# 5__schdoc.net
KiCad netlist of a schematic drawn in Altium Designer
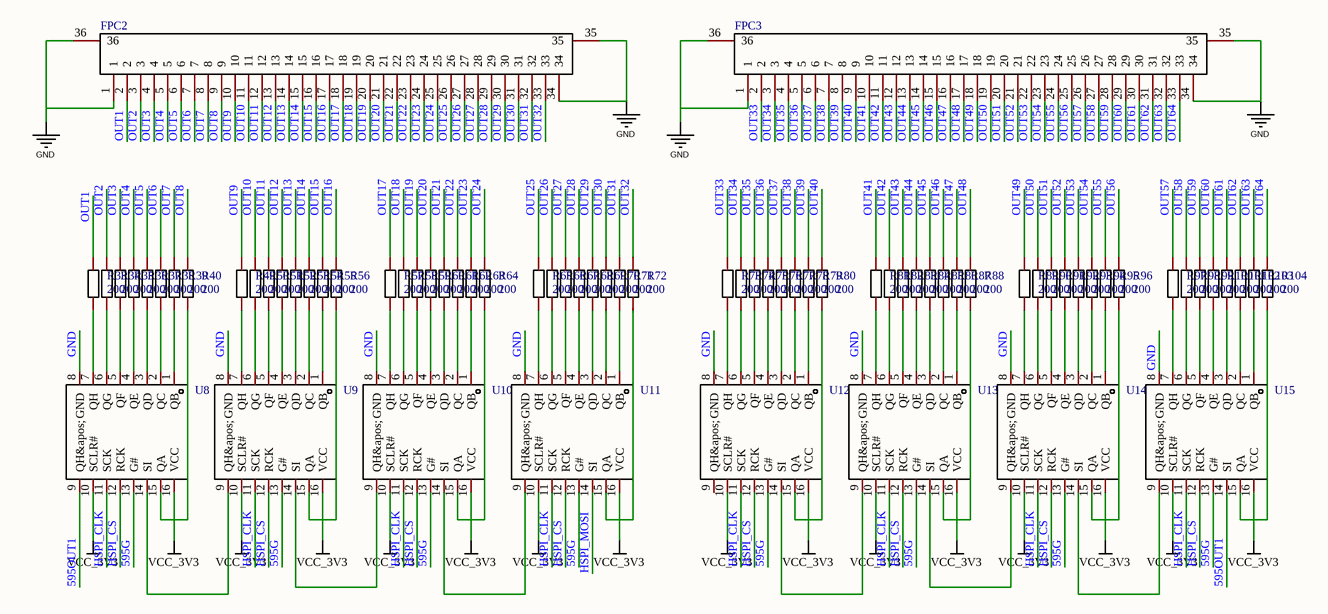
[diagram p0: 5_移位寄存器部分.schdoc.schdoc]

(export (version "E")
  (design (tool "Eeschema 10.0.6"))
  (components
    (comp (ref "FPC2")
      (value "AFC07-S34FCC-00")
      (description "锁定特性:抽屉式;触点类型:下接;触点数量:34P;间距:0.5mm;安装类型:卧贴;")
      (fields (field (name "MANUFACTURER") "JS(钜硕电子)"))
      (libsource (lib "altium-import") (part "root_1_AFC07-S34FCC-00_"))
    )
    (comp (ref "FPC3")
      (value "AFC07-S34FCC-00")
      (description "锁定特性:抽屉式;触点类型:下接;触点数量:34P;间距:0.5mm;安装类型:卧贴;")
      (fields (field (name "MANUFACTURER") "JS(钜硕电子)"))
      (libsource (lib "altium-import") (part "root_1_AFC07-S34FCC-00_"))
    )
    (comp (ref "R33")
      (value "200")
      (fields (field (name "Comment") "Res_0402"))
      (libsource (lib "altium-import") (part "root_1_Res_0402_"))
    )
    (comp (ref "R34")
      (value "200")
      (fields (field (name "Comment") "Res_0402"))
      (libsource (lib "altium-import") (part "root_1_Res_0402_"))
    )
    (comp (ref "R35")
      (value "200")
      (fields (field (name "Comment") "Res_0402"))
      (libsource (lib "altium-import") (part "root_1_Res_0402_"))
    )
    (comp (ref "R36")
      (value "200")
      (fields (field (name "Comment") "Res_0402"))
      (libsource (lib "altium-import") (part "root_1_Res_0402_"))
    )
    (comp (ref "R37")
      (value "200")
      (fields (field (name "Comment") "Res_0402"))
      (libsource (lib "altium-import") (part "root_1_Res_0402_"))
    )
    (comp (ref "R38")
      (value "200")
      (fields (field (name "Comment") "Res_0402"))
      (libsource (lib "altium-import") (part "root_1_Res_0402_"))
    )
    (comp (ref "R39")
      (value "200")
      (fields (field (name "Comment") "Res_0402"))
      (libsource (lib "altium-import") (part "root_1_Res_0402_"))
    )
    (comp (ref "R40")
      (value "200")
      (fields (field (name "Comment") "Res_0402"))
      (libsource (lib "altium-import") (part "root_1_Res_0402_"))
    )
    (comp (ref "R49")
      (value "200")
      (fields (field (name "Comment") "Res_0402"))
      (libsource (lib "altium-import") (part "root_1_Res_0402_"))
    )
    (comp (ref "R50")
      (value "200")
      (fields (field (name "Comment") "Res_0402"))
      (libsource (lib "altium-import") (part "root_1_Res_0402_"))
    )
    (comp (ref "R51")
      (value "200")
      (fields (field (name "Comment") "Res_0402"))
      (libsource (lib "altium-import") (part "root_1_Res_0402_"))
    )
    (comp (ref "R52")
      (value "200")
      (fields (field (name "Comment") "Res_0402"))
      (libsource (lib "altium-import") (part "root_1_Res_0402_"))
    )
    (comp (ref "R53")
      (value "200")
      (fields (field (name "Comment") "Res_0402"))
      (libsource (lib "altium-import") (part "root_1_Res_0402_"))
    )
    (comp (ref "R54")
      (value "200")
      (fields (field (name "Comment") "Res_0402"))
      (libsource (lib "altium-import") (part "root_1_Res_0402_"))
    )
    (comp (ref "R55")
      (value "200")
      (fields (field (name "Comment") "Res_0402"))
      (libsource (lib "altium-import") (part "root_1_Res_0402_"))
    )
    (comp (ref "R56")
      (value "200")
      (fields (field (name "Comment") "Res_0402"))
      (libsource (lib "altium-import") (part "root_1_Res_0402_"))
    )
    (comp (ref "R57")
      (value "200")
      (fields (field (name "Comment") "Res_0402"))
      (libsource (lib "altium-import") (part "root_1_Res_0402_"))
    )
    (comp (ref "R58")
      (value "200")
      (fields (field (name "Comment") "Res_0402"))
      (libsource (lib "altium-import") (part "root_1_Res_0402_"))
    )
    (comp (ref "R59")
      (value "200")
      (fields (field (name "Comment") "Res_0402"))
      (libsource (lib "altium-import") (part "root_1_Res_0402_"))
    )
    (comp (ref "R60")
      (value "200")
      (fields (field (name "Comment") "Res_0402"))
      (libsource (lib "altium-import") (part "root_1_Res_0402_"))
    )
    (comp (ref "R61")
      (value "200")
      (fields (field (name "Comment") "Res_0402"))
      (libsource (lib "altium-import") (part "root_1_Res_0402_"))
    )
    (comp (ref "R62")
      (value "200")
      (fields (field (name "Comment") "Res_0402"))
      (libsource (lib "altium-import") (part "root_1_Res_0402_"))
    )
    (comp (ref "R63")
      (value "200")
      (fields (field (name "Comment") "Res_0402"))
      (libsource (lib "altium-import") (part "root_1_Res_0402_"))
    )
    (comp (ref "R64")
      (value "200")
      (fields (field (name "Comment") "Res_0402"))
      (libsource (lib "altium-import") (part "root_1_Res_0402_"))
    )
    (comp (ref "R65")
      (value "200")
      (fields (field (name "Comment") "Res_0402"))
      (libsource (lib "altium-import") (part "root_1_Res_0402_"))
    )
    (comp (ref "R66")
      (value "200")
      (fields (field (name "Comment") "Res_0402"))
      (libsource (lib "altium-import") (part "root_1_Res_0402_"))
    )
    (comp (ref "R67")
      (value "200")
      (fields (field (name "Comment") "Res_0402"))
      (libsource (lib "altium-import") (part "root_1_Res_0402_"))
    )
    (comp (ref "R68")
      (value "200")
      (fields (field (name "Comment") "Res_0402"))
      (libsource (lib "altium-import") (part "root_1_Res_0402_"))
    )
    (comp (ref "R69")
      (value "200")
      (fields (field (name "Comment") "Res_0402"))
      (libsource (lib "altium-import") (part "root_1_Res_0402_"))
    )
    (comp (ref "R70")
      (value "200")
      (fields (field (name "Comment") "Res_0402"))
      (libsource (lib "altium-import") (part "root_1_Res_0402_"))
    )
    (comp (ref "R71")
      (value "200")
      (fields (field (name "Comment") "Res_0402"))
      (libsource (lib "altium-import") (part "root_1_Res_0402_"))
    )
    (comp (ref "R72")
      (value "200")
      (fields (field (name "Comment") "Res_0402"))
      (libsource (lib "altium-import") (part "root_1_Res_0402_"))
    )
    (comp (ref "R73")
      (value "200")
      (fields (field (name "Comment") "Res_0402"))
      (libsource (lib "altium-import") (part "root_1_Res_0402_"))
    )
    (comp (ref "R74")
      (value "200")
      (fields (field (name "Comment") "Res_0402"))
      (libsource (lib "altium-import") (part "root_1_Res_0402_"))
    )
    (comp (ref "R75")
      (value "200")
      (fields (field (name "Comment") "Res_0402"))
      (libsource (lib "altium-import") (part "root_1_Res_0402_"))
    )
    (comp (ref "R76")
      (value "200")
      (fields (field (name "Comment") "Res_0402"))
      (libsource (lib "altium-import") (part "root_1_Res_0402_"))
    )
    (comp (ref "R77")
      (value "200")
      (fields (field (name "Comment") "Res_0402"))
      (libsource (lib "altium-import") (part "root_1_Res_0402_"))
    )
    (comp (ref "R78")
      (value "200")
      (fields (field (name "Comment") "Res_0402"))
      (libsource (lib "altium-import") (part "root_1_Res_0402_"))
    )
    (comp (ref "R79")
      (value "200")
      (fields (field (name "Comment") "Res_0402"))
      (libsource (lib "altium-import") (part "root_1_Res_0402_"))
    )
    (comp (ref "R80")
      (value "200")
      (fields (field (name "Comment") "Res_0402"))
      (libsource (lib "altium-import") (part "root_1_Res_0402_"))
    )
    (comp (ref "R81")
      (value "200")
      (fields (field (name "Comment") "Res_0402"))
      (libsource (lib "altium-import") (part "root_1_Res_0402_"))
    )
    (comp (ref "R82")
      (value "200")
      (fields (field (name "Comment") "Res_0402"))
      (libsource (lib "altium-import") (part "root_1_Res_0402_"))
    )
    (comp (ref "R83")
      (value "200")
      (fields (field (name "Comment") "Res_0402"))
      (libsource (lib "altium-import") (part "root_1_Res_0402_"))
    )
    (comp (ref "R84")
      (value "200")
      (fields (field (name "Comment") "Res_0402"))
      (libsource (lib "altium-import") (part "root_1_Res_0402_"))
    )
    (comp (ref "R85")
      (value "200")
      (fields (field (name "Comment") "Res_0402"))
      (libsource (lib "altium-import") (part "root_1_Res_0402_"))
    )
    (comp (ref "R86")
      (value "200")
      (fields (field (name "Comment") "Res_0402"))
      (libsource (lib "altium-import") (part "root_1_Res_0402_"))
    )
    (comp (ref "R87")
      (value "200")
      (fields (field (name "Comment") "Res_0402"))
      (libsource (lib "altium-import") (part "root_1_Res_0402_"))
    )
    (comp (ref "R88")
      (value "200")
      (fields (field (name "Comment") "Res_0402"))
      (libsource (lib "altium-import") (part "root_1_Res_0402_"))
    )
    (comp (ref "R89")
      (value "200")
      (fields (field (name "Comment") "Res_0402"))
      (libsource (lib "altium-import") (part "root_1_Res_0402_"))
    )
    (comp (ref "R90")
      (value "200")
      (fields (field (name "Comment") "Res_0402"))
      (libsource (lib "altium-import") (part "root_1_Res_0402_"))
    )
    (comp (ref "R91")
      (value "200")
      (fields (field (name "Comment") "Res_0402"))
      (libsource (lib "altium-import") (part "root_1_Res_0402_"))
    )
    (comp (ref "R92")
      (value "200")
      (fields (field (name "Comment") "Res_0402"))
      (libsource (lib "altium-import") (part "root_1_Res_0402_"))
    )
    (comp (ref "R93")
      (value "200")
      (fields (field (name "Comment") "Res_0402"))
      (libsource (lib "altium-import") (part "root_1_Res_0402_"))
    )
    (comp (ref "R94")
      (value "200")
      (fields (field (name "Comment") "Res_0402"))
      (libsource (lib "altium-import") (part "root_1_Res_0402_"))
    )
    (comp (ref "R95")
      (value "200")
      (fields (field (name "Comment") "Res_0402"))
      (libsource (lib "altium-import") (part "root_1_Res_0402_"))
    )
    (comp (ref "R96")
      (value "200")
      (fields (field (name "Comment") "Res_0402"))
      (libsource (lib "altium-import") (part "root_1_Res_0402_"))
    )
    (comp (ref "R97")
      (value "200")
      (fields (field (name "Comment") "Res_0402"))
      (libsource (lib "altium-import") (part "root_1_Res_0402_"))
    )
    (comp (ref "R98")
      (value "200")
      (fields (field (name "Comment") "Res_0402"))
      (libsource (lib "altium-import") (part "root_1_Res_0402_"))
    )
    (comp (ref "R99")
      (value "200")
      (fields (field (name "Comment") "Res_0402"))
      (libsource (lib "altium-import") (part "root_1_Res_0402_"))
    )
    (comp (ref "R100")
      (value "200")
      (fields (field (name "Comment") "Res_0402"))
      (libsource (lib "altium-import") (part "root_1_Res_0402_"))
    )
    (comp (ref "R101")
      (value "200")
      (fields (field (name "Comment") "Res_0402"))
      (libsource (lib "altium-import") (part "root_1_Res_0402_"))
    )
    (comp (ref "R102")
      (value "200")
      (fields (field (name "Comment") "Res_0402"))
      (libsource (lib "altium-import") (part "root_1_Res_0402_"))
    )
    (comp (ref "R103")
      (value "200")
      (fields (field (name "Comment") "Res_0402"))
      (libsource (lib "altium-import") (part "root_1_Res_0402_"))
    )
    (comp (ref "R104")
      (value "200")
      (fields (field (name "Comment") "Res_0402"))
      (libsource (lib "altium-import") (part "root_1_Res_0402_"))
    )
    (comp (ref "U8")
      (value "74HC595D_C431479")
      (description "功能:串行至串行或并行;电源电压:2V~6V;元件数:1;每个元件位数:8;")
      (fields (field (name "MANUFACTURER") "TOSHIBA(东芝)") (field (name "MANUFACTURER PART") "74HC595D"))
      (libsource (lib "altium-import") (part "root_3_74HC595D_C431479_"))
    )
    (comp (ref "U9")
      (value "74HC595D_C431479")
      (description "功能:串行至串行或并行;电源电压:2V~6V;元件数:1;每个元件位数:8;")
      (fields (field (name "MANUFACTURER") "TOSHIBA(东芝)") (field (name "MANUFACTURER PART") "74HC595D"))
      (libsource (lib "altium-import") (part "root_3_74HC595D_C431479_"))
    )
    (comp (ref "U10")
      (value "74HC595D_C431479")
      (description "功能:串行至串行或并行;电源电压:2V~6V;元件数:1;每个元件位数:8;")
      (fields (field (name "MANUFACTURER") "TOSHIBA(东芝)") (field (name "MANUFACTURER PART") "74HC595D"))
      (libsource (lib "altium-import") (part "root_3_74HC595D_C431479_"))
    )
    (comp (ref "U11")
      (value "74HC595D_C431479")
      (description "功能:串行至串行或并行;电源电压:2V~6V;元件数:1;每个元件位数:8;")
      (fields (field (name "MANUFACTURER") "TOSHIBA(东芝)") (field (name "MANUFACTURER PART") "74HC595D"))
      (libsource (lib "altium-import") (part "root_3_74HC595D_C431479_"))
    )
    (comp (ref "U12")
      (value "74HC595D_C431479")
      (description "功能:串行至串行或并行;电源电压:2V~6V;元件数:1;每个元件位数:8;")
      (fields (field (name "MANUFACTURER") "TOSHIBA(东芝)") (field (name "MANUFACTURER PART") "74HC595D"))
      (libsource (lib "altium-import") (part "root_3_74HC595D_C431479_"))
    )
    (comp (ref "U13")
      (value "74HC595D_C431479")
      (description "功能:串行至串行或并行;电源电压:2V~6V;元件数:1;每个元件位数:8;")
      (fields (field (name "MANUFACTURER") "TOSHIBA(东芝)") (field (name "MANUFACTURER PART") "74HC595D"))
      (libsource (lib "altium-import") (part "root_3_74HC595D_C431479_"))
    )
    (comp (ref "U14")
      (value "74HC595D_C431479")
      (description "功能:串行至串行或并行;电源电压:2V~6V;元件数:1;每个元件位数:8;")
      (fields (field (name "MANUFACTURER") "TOSHIBA(东芝)") (field (name "MANUFACTURER PART") "74HC595D"))
      (libsource (lib "altium-import") (part "root_3_74HC595D_C431479_"))
    )
    (comp (ref "U15")
      (value "74HC595D_C431479")
      (description "功能:串行至串行或并行;电源电压:2V~6V;元件数:1;每个元件位数:8;")
      (fields (field (name "MANUFACTURER") "TOSHIBA(东芝)") (field (name "MANUFACTURER PART") "74HC595D"))
      (libsource (lib "altium-import") (part "root_3_74HC595D_C431479_"))
    )
  )
  (nets
    (net (code "1") (name "/595G") (class "Default")
      (node (ref "U10") (pin "13") (pinfunction "G#_13") (pintype "passive"))
      (node (ref "U11") (pin "13") (pinfunction "G#_13") (pintype "passive"))
      (node (ref "U12") (pin "13") (pinfunction "G#_13") (pintype "passive"))
      (node (ref "U13") (pin "13") (pinfunction "G#_13") (pintype "passive"))
      (node (ref "U14") (pin "13") (pinfunction "G#_13") (pintype "passive"))
      (node (ref "U15") (pin "13") (pinfunction "G#_13") (pintype "passive"))
      (node (ref "U8") (pin "13") (pinfunction "G#_13") (pintype "passive"))
      (node (ref "U9") (pin "13") (pinfunction "G#_13") (pintype "passive"))
    )
    (net (code "2") (name "/595OUT1") (class "Default")
      (node (ref "U15") (pin "14") (pinfunction "SI_14") (pintype "passive"))
      (node (ref "U8") (pin "9") (pinfunction "QH&apos;_9") (pintype "passive"))
    )
    (net (code "3") (name "/HSPI_CLK") (class "Default")
      (node (ref "U10") (pin "11") (pinfunction "SCK_11") (pintype "passive"))
      (node (ref "U11") (pin "11") (pinfunction "SCK_11") (pintype "passive"))
      (node (ref "U12") (pin "11") (pinfunction "SCK_11") (pintype "passive"))
      (node (ref "U13") (pin "11") (pinfunction "SCK_11") (pintype "passive"))
      (node (ref "U14") (pin "11") (pinfunction "SCK_11") (pintype "passive"))
      (node (ref "U15") (pin "11") (pinfunction "SCK_11") (pintype "passive"))
      (node (ref "U8") (pin "11") (pinfunction "SCK_11") (pintype "passive"))
      (node (ref "U9") (pin "11") (pinfunction "SCK_11") (pintype "passive"))
    )
    (net (code "4") (name "/HSPI_CS") (class "Default")
      (node (ref "U10") (pin "12") (pinfunction "RCK_12") (pintype "passive"))
      (node (ref "U11") (pin "12") (pinfunction "RCK_12") (pintype "passive"))
      (node (ref "U12") (pin "12") (pinfunction "RCK_12") (pintype "passive"))
      (node (ref "U13") (pin "12") (pinfunction "RCK_12") (pintype "passive"))
      (node (ref "U14") (pin "12") (pinfunction "RCK_12") (pintype "passive"))
      (node (ref "U15") (pin "12") (pinfunction "RCK_12") (pintype "passive"))
      (node (ref "U8") (pin "12") (pinfunction "RCK_12") (pintype "passive"))
      (node (ref "U9") (pin "12") (pinfunction "RCK_12") (pintype "passive"))
    )
    (net (code "5") (name "/HSPI_MOSI") (class "Default")
      (node (ref "U11") (pin "14") (pinfunction "SI_14") (pintype "passive"))
    )
    (net (code "6") (name "/OUT1") (class "Default")
      (node (ref "FPC2") (pin "2") (pinfunction "2_2") (pintype "passive"))
      (node (ref "R33") (pin "2") (pinfunction "2_2") (pintype "passive"))
    )
    (net (code "7") (name "/OUT2") (class "Default")
      (node (ref "FPC2") (pin "3") (pinfunction "3_3") (pintype "passive"))
      (node (ref "R34") (pin "2") (pinfunction "2_2") (pintype "passive"))
    )
    (net (code "8") (name "/OUT3") (class "Default")
      (node (ref "FPC2") (pin "4") (pinfunction "4_4") (pintype "passive"))
      (node (ref "R35") (pin "2") (pinfunction "2_2") (pintype "passive"))
    )
    (net (code "9") (name "/OUT4") (class "Default")
      (node (ref "FPC2") (pin "5") (pinfunction "5_5") (pintype "passive"))
      (node (ref "R36") (pin "2") (pinfunction "2_2") (pintype "passive"))
    )
    (net (code "10") (name "/OUT5") (class "Default")
      (node (ref "FPC2") (pin "6") (pinfunction "6_6") (pintype "passive"))
      (node (ref "R37") (pin "2") (pinfunction "2_2") (pintype "passive"))
    )
    (net (code "11") (name "/OUT6") (class "Default")
      (node (ref "FPC2") (pin "7") (pinfunction "7_7") (pintype "passive"))
      (node (ref "R38") (pin "2") (pinfunction "2_2") (pintype "passive"))
    )
    (net (code "12") (name "/OUT7") (class "Default")
      (node (ref "FPC2") (pin "8") (pinfunction "8_8") (pintype "passive"))
      (node (ref "R39") (pin "2") (pinfunction "2_2") (pintype "passive"))
    )
    (net (code "13") (name "/OUT8") (class "Default")
      (node (ref "FPC2") (pin "9") (pinfunction "9_9") (pintype "passive"))
      (node (ref "R40") (pin "2") (pinfunction "2_2") (pintype "passive"))
    )
    (net (code "14") (name "/OUT9") (class "Default")
      (node (ref "FPC2") (pin "10") (pinfunction "10_10") (pintype "passive"))
      (node (ref "R49") (pin "2") (pinfunction "2_2") (pintype "passive"))
    )
    (net (code "15") (name "/OUT10") (class "Default")
      (node (ref "FPC2") (pin "11") (pinfunction "11_11") (pintype "passive"))
      (node (ref "R50") (pin "2") (pinfunction "2_2") (pintype "passive"))
    )
    (net (code "16") (name "/OUT11") (class "Default")
      (node (ref "FPC2") (pin "12") (pinfunction "12_12") (pintype "passive"))
      (node (ref "R51") (pin "2") (pinfunction "2_2") (pintype "passive"))
    )
    (net (code "17") (name "/OUT12") (class "Default")
      (node (ref "FPC2") (pin "13") (pinfunction "13_13") (pintype "passive"))
      (node (ref "R52") (pin "2") (pinfunction "2_2") (pintype "passive"))
    )
    (net (code "18") (name "/OUT13") (class "Default")
      (node (ref "FPC2") (pin "14") (pinfunction "14_14") (pintype "passive"))
      (node (ref "R53") (pin "2") (pinfunction "2_2") (pintype "passive"))
    )
    (net (code "19") (name "/OUT14") (class "Default")
      (node (ref "FPC2") (pin "15") (pinfunction "15_15") (pintype "passive"))
      (node (ref "R54") (pin "2") (pinfunction "2_2") (pintype "passive"))
    )
    (net (code "20") (name "/OUT15") (class "Default")
      (node (ref "FPC2") (pin "16") (pinfunction "16_16") (pintype "passive"))
      (node (ref "R55") (pin "2") (pinfunction "2_2") (pintype "passive"))
    )
    (net (code "21") (name "/OUT16") (class "Default")
      (node (ref "FPC2") (pin "17") (pinfunction "17_17") (pintype "passive"))
      (node (ref "R56") (pin "2") (pinfunction "2_2") (pintype "passive"))
    )
    (net (code "22") (name "/OUT17") (class "Default")
      (node (ref "FPC2") (pin "18") (pinfunction "18_18") (pintype "passive"))
      (node (ref "R57") (pin "2") (pinfunction "2_2") (pintype "passive"))
    )
    (net (code "23") (name "/OUT18") (class "Default")
      (node (ref "FPC2") (pin "19") (pinfunction "19_19") (pintype "passive"))
      (node (ref "R58") (pin "2") (pinfunction "2_2") (pintype "passive"))
    )
    (net (code "24") (name "/OUT19") (class "Default")
      (node (ref "FPC2") (pin "20") (pinfunction "20_20") (pintype "passive"))
      (node (ref "R59") (pin "2") (pinfunction "2_2") (pintype "passive"))
    )
    (net (code "25") (name "/OUT20") (class "Default")
      (node (ref "FPC2") (pin "21") (pinfunction "21_21") (pintype "passive"))
      (node (ref "R60") (pin "2") (pinfunction "2_2") (pintype "passive"))
    )
    (net (code "26") (name "/OUT21") (class "Default")
      (node (ref "FPC2") (pin "22") (pinfunction "22_22") (pintype "passive"))
      (node (ref "R61") (pin "2") (pinfunction "2_2") (pintype "passive"))
    )
    (net (code "27") (name "/OUT22") (class "Default")
      (node (ref "FPC2") (pin "23") (pinfunction "23_23") (pintype "passive"))
      (node (ref "R62") (pin "2") (pinfunction "2_2") (pintype "passive"))
    )
    (net (code "28") (name "/OUT23") (class "Default")
      (node (ref "FPC2") (pin "24") (pinfunction "24_24") (pintype "passive"))
      (node (ref "R63") (pin "2") (pinfunction "2_2") (pintype "passive"))
    )
    (net (code "29") (name "/OUT24") (class "Default")
      (node (ref "FPC2") (pin "25") (pinfunction "25_25") (pintype "passive"))
      (node (ref "R64") (pin "2") (pinfunction "2_2") (pintype "passive"))
    )
    (net (code "30") (name "/OUT25") (class "Default")
      (node (ref "FPC2") (pin "26") (pinfunction "26_26") (pintype "passive"))
      (node (ref "R65") (pin "2") (pinfunction "2_2") (pintype "passive"))
    )
    (net (code "31") (name "/OUT26") (class "Default")
      (node (ref "FPC2") (pin "27") (pinfunction "27_27") (pintype "passive"))
      (node (ref "R66") (pin "2") (pinfunction "2_2") (pintype "passive"))
    )
    (net (code "32") (name "/OUT27") (class "Default")
      (node (ref "FPC2") (pin "28") (pinfunction "28_28") (pintype "passive"))
      (node (ref "R67") (pin "2") (pinfunction "2_2") (pintype "passive"))
    )
    (net (code "33") (name "/OUT28") (class "Default")
      (node (ref "FPC2") (pin "29") (pinfunction "29_29") (pintype "passive"))
      (node (ref "R68") (pin "2") (pinfunction "2_2") (pintype "passive"))
    )
    (net (code "34") (name "/OUT29") (class "Default")
      (node (ref "FPC2") (pin "30") (pinfunction "30_30") (pintype "passive"))
      (node (ref "R69") (pin "2") (pinfunction "2_2") (pintype "passive"))
    )
    (net (code "35") (name "/OUT30") (class "Default")
      (node (ref "FPC2") (pin "31") (pinfunction "31_31") (pintype "passive"))
      (node (ref "R70") (pin "2") (pinfunction "2_2") (pintype "passive"))
    )
    (net (code "36") (name "/OUT31") (class "Default")
      (node (ref "FPC2") (pin "32") (pinfunction "32_32") (pintype "passive"))
      (node (ref "R71") (pin "2") (pinfunction "2_2") (pintype "passive"))
    )
    (net (code "37") (name "/OUT32") (class "Default")
      (node (ref "FPC2") (pin "33") (pinfunction "33_33") (pintype "passive"))
      (node (ref "R72") (pin "2") (pinfunction "2_2") (pintype "passive"))
    )
    (net (code "38") (name "/OUT33") (class "Default")
      (node (ref "FPC3") (pin "2") (pinfunction "2_2") (pintype "passive"))
      (node (ref "R73") (pin "2") (pinfunction "2_2") (pintype "passive"))
    )
    (net (code "39") (name "/OUT34") (class "Default")
      (node (ref "FPC3") (pin "3") (pinfunction "3_3") (pintype "passive"))
      (node (ref "R74") (pin "2") (pinfunction "2_2") (pintype "passive"))
    )
    (net (code "40") (name "/OUT35") (class "Default")
      (node (ref "FPC3") (pin "4") (pinfunction "4_4") (pintype "passive"))
      (node (ref "R75") (pin "2") (pinfunction "2_2") (pintype "passive"))
    )
    (net (code "41") (name "/OUT36") (class "Default")
      (node (ref "FPC3") (pin "5") (pinfunction "5_5") (pintype "passive"))
      (node (ref "R76") (pin "2") (pinfunction "2_2") (pintype "passive"))
    )
    (net (code "42") (name "/OUT37") (class "Default")
      (node (ref "FPC3") (pin "6") (pinfunction "6_6") (pintype "passive"))
      (node (ref "R77") (pin "2") (pinfunction "2_2") (pintype "passive"))
    )
    (net (code "43") (name "/OUT38") (class "Default")
      (node (ref "FPC3") (pin "7") (pinfunction "7_7") (pintype "passive"))
      (node (ref "R78") (pin "2") (pinfunction "2_2") (pintype "passive"))
    )
    (net (code "44") (name "/OUT39") (class "Default")
      (node (ref "FPC3") (pin "8") (pinfunction "8_8") (pintype "passive"))
      (node (ref "R79") (pin "2") (pinfunction "2_2") (pintype "passive"))
    )
    (net (code "45") (name "/OUT40") (class "Default")
      (node (ref "FPC3") (pin "9") (pinfunction "9_9") (pintype "passive"))
      (node (ref "R80") (pin "2") (pinfunction "2_2") (pintype "passive"))
    )
    (net (code "46") (name "/OUT41") (class "Default")
      (node (ref "FPC3") (pin "10") (pinfunction "10_10") (pintype "passive"))
      (node (ref "R81") (pin "2") (pinfunction "2_2") (pintype "passive"))
    )
    (net (code "47") (name "/OUT42") (class "Default")
      (node (ref "FPC3") (pin "11") (pinfunction "11_11") (pintype "passive"))
      (node (ref "R82") (pin "2") (pinfunction "2_2") (pintype "passive"))
    )
    (net (code "48") (name "/OUT43") (class "Default")
      (node (ref "FPC3") (pin "12") (pinfunction "12_12") (pintype "passive"))
      (node (ref "R83") (pin "2") (pinfunction "2_2") (pintype "passive"))
    )
    (net (code "49") (name "/OUT44") (class "Default")
      (node (ref "FPC3") (pin "13") (pinfunction "13_13") (pintype "passive"))
      (node (ref "R84") (pin "2") (pinfunction "2_2") (pintype "passive"))
    )
    (net (code "50") (name "/OUT45") (class "Default")
      (node (ref "FPC3") (pin "14") (pinfunction "14_14") (pintype "passive"))
      (node (ref "R85") (pin "2") (pinfunction "2_2") (pintype "passive"))
    )
    (net (code "51") (name "/OUT46") (class "Default")
      (node (ref "FPC3") (pin "15") (pinfunction "15_15") (pintype "passive"))
      (node (ref "R86") (pin "2") (pinfunction "2_2") (pintype "passive"))
    )
    (net (code "52") (name "/OUT47") (class "Default")
      (node (ref "FPC3") (pin "16") (pinfunction "16_16") (pintype "passive"))
      (node (ref "R87") (pin "2") (pinfunction "2_2") (pintype "passive"))
    )
    (net (code "53") (name "/OUT48") (class "Default")
      (node (ref "FPC3") (pin "17") (pinfunction "17_17") (pintype "passive"))
      (node (ref "R88") (pin "2") (pinfunction "2_2") (pintype "passive"))
    )
    (net (code "54") (name "/OUT49") (class "Default")
      (node (ref "FPC3") (pin "18") (pinfunction "18_18") (pintype "passive"))
      (node (ref "R89") (pin "2") (pinfunction "2_2") (pintype "passive"))
    )
    (net (code "55") (name "/OUT50") (class "Default")
      (node (ref "FPC3") (pin "19") (pinfunction "19_19") (pintype "passive"))
      (node (ref "R90") (pin "2") (pinfunction "2_2") (pintype "passive"))
    )
    (net (code "56") (name "/OUT51") (class "Default")
      (node (ref "FPC3") (pin "20") (pinfunction "20_20") (pintype "passive"))
      (node (ref "R91") (pin "2") (pinfunction "2_2") (pintype "passive"))
    )
    (net (code "57") (name "/OUT52") (class "Default")
      (node (ref "FPC3") (pin "21") (pinfunction "21_21") (pintype "passive"))
      (node (ref "R92") (pin "2") (pinfunction "2_2") (pintype "passive"))
    )
    (net (code "58") (name "/OUT53") (class "Default")
      (node (ref "FPC3") (pin "22") (pinfunction "22_22") (pintype "passive"))
      (node (ref "R93") (pin "2") (pinfunction "2_2") (pintype "passive"))
    )
    (net (code "59") (name "/OUT54") (class "Default")
      (node (ref "FPC3") (pin "23") (pinfunction "23_23") (pintype "passive"))
      (node (ref "R94") (pin "2") (pinfunction "2_2") (pintype "passive"))
    )
    (net (code "60") (name "/OUT55") (class "Default")
      (node (ref "FPC3") (pin "24") (pinfunction "24_24") (pintype "passive"))
      (node (ref "R95") (pin "2") (pinfunction "2_2") (pintype "passive"))
    )
    (net (code "61") (name "/OUT56") (class "Default")
      (node (ref "FPC3") (pin "25") (pinfunction "25_25") (pintype "passive"))
      (node (ref "R96") (pin "2") (pinfunction "2_2") (pintype "passive"))
    )
    (net (code "62") (name "/OUT57") (class "Default")
      (node (ref "FPC3") (pin "26") (pinfunction "26_26") (pintype "passive"))
      (node (ref "R97") (pin "2") (pinfunction "2_2") (pintype "passive"))
    )
    (net (code "63") (name "/OUT58") (class "Default")
      (node (ref "FPC3") (pin "27") (pinfunction "27_27") (pintype "passive"))
      (node (ref "R98") (pin "2") (pinfunction "2_2") (pintype "passive"))
    )
    (net (code "64") (name "/OUT59") (class "Default")
      (node (ref "FPC3") (pin "28") (pinfunction "28_28") (pintype "passive"))
      (node (ref "R99") (pin "2") (pinfunction "2_2") (pintype "passive"))
    )
    (net (code "65") (name "/OUT60") (class "Default")
      (node (ref "FPC3") (pin "29") (pinfunction "29_29") (pintype "passive"))
      (node (ref "R100") (pin "2") (pinfunction "2_2") (pintype "passive"))
    )
    (net (code "66") (name "/OUT61") (class "Default")
      (node (ref "FPC3") (pin "30") (pinfunction "30_30") (pintype "passive"))
      (node (ref "R101") (pin "2") (pinfunction "2_2") (pintype "passive"))
    )
    (net (code "67") (name "/OUT62") (class "Default")
      (node (ref "FPC3") (pin "31") (pinfunction "31_31") (pintype "passive"))
      (node (ref "R102") (pin "2") (pinfunction "2_2") (pintype "passive"))
    )
    (net (code "68") (name "/OUT63") (class "Default")
      (node (ref "FPC3") (pin "32") (pinfunction "32_32") (pintype "passive"))
      (node (ref "R103") (pin "2") (pinfunction "2_2") (pintype "passive"))
    )
    (net (code "69") (name "/OUT64") (class "Default")
      (node (ref "FPC3") (pin "33") (pinfunction "33_33") (pintype "passive"))
      (node (ref "R104") (pin "2") (pinfunction "2_2") (pintype "passive"))
    )
    (net (code "70") (name "GND") (class "Default")
      (node (ref "FPC2") (pin "1") (pinfunction "1_1") (pintype "passive"))
      (node (ref "FPC2") (pin "34") (pinfunction "34_34") (pintype "passive"))
      (node (ref "FPC2") (pin "35") (pinfunction "35_35") (pintype "passive"))
      (node (ref "FPC2") (pin "36") (pinfunction "36_36") (pintype "passive"))
      (node (ref "FPC3") (pin "1") (pinfunction "1_1") (pintype "passive"))
      (node (ref "FPC3") (pin "34") (pinfunction "34_34") (pintype "passive"))
      (node (ref "FPC3") (pin "35") (pinfunction "35_35") (pintype "passive"))
      (node (ref "FPC3") (pin "36") (pinfunction "36_36") (pintype "passive"))
      (node (ref "U10") (pin "8") (pinfunction "GND_8") (pintype "passive"))
      (node (ref "U11") (pin "8") (pinfunction "GND_8") (pintype "passive"))
      (node (ref "U12") (pin "8") (pinfunction "GND_8") (pintype "passive"))
      (node (ref "U13") (pin "8") (pinfunction "GND_8") (pintype "passive"))
      (node (ref "U14") (pin "8") (pinfunction "GND_8") (pintype "passive"))
      (node (ref "U15") (pin "8") (pinfunction "GND_8") (pintype "passive"))
      (node (ref "U8") (pin "8") (pinfunction "GND_8") (pintype "passive"))
      (node (ref "U9") (pin "8") (pinfunction "GND_8") (pintype "passive"))
    )
    (net (code "71") (name "Net-(U8-QA)") (class "Default")
      (node (ref "R40") (pin "1") (pinfunction "1_1") (pintype "passive"))
      (node (ref "U8") (pin "15") (pinfunction "QA_15") (pintype "passive"))
    )
    (net (code "72") (name "Net-(U8-QB)") (class "Default")
      (node (ref "R39") (pin "1") (pinfunction "1_1") (pintype "passive"))
      (node (ref "U8") (pin "1") (pinfunction "QB_1") (pintype "passive"))
    )
    (net (code "73") (name "Net-(U8-QC)") (class "Default")
      (node (ref "R38") (pin "1") (pinfunction "1_1") (pintype "passive"))
      (node (ref "U8") (pin "2") (pinfunction "QC_2") (pintype "passive"))
    )
    (net (code "74") (name "Net-(U8-QD)") (class "Default")
      (node (ref "R37") (pin "1") (pinfunction "1_1") (pintype "passive"))
      (node (ref "U8") (pin "3") (pinfunction "QD_3") (pintype "passive"))
    )
    (net (code "75") (name "Net-(U8-QE)") (class "Default")
      (node (ref "R36") (pin "1") (pinfunction "1_1") (pintype "passive"))
      (node (ref "U8") (pin "4") (pinfunction "QE_4") (pintype "passive"))
    )
    (net (code "76") (name "Net-(U8-QF)") (class "Default")
      (node (ref "R35") (pin "1") (pinfunction "1_1") (pintype "passive"))
      (node (ref "U8") (pin "5") (pinfunction "QF_5") (pintype "passive"))
    )
    (net (code "77") (name "Net-(U8-QG)") (class "Default")
      (node (ref "R34") (pin "1") (pinfunction "1_1") (pintype "passive"))
      (node (ref "U8") (pin "6") (pinfunction "QG_6") (pintype "passive"))
    )
    (net (code "78") (name "Net-(U8-QH)") (class "Default")
      (node (ref "R33") (pin "1") (pinfunction "1_1") (pintype "passive"))
      (node (ref "U8") (pin "7") (pinfunction "QH_7") (pintype "passive"))
    )
    (net (code "79") (name "Net-(U8-SI)") (class "Default")
      (node (ref "U8") (pin "14") (pinfunction "SI_14") (pintype "passive"))
      (node (ref "U9") (pin "9") (pinfunction "QH&apos;_9") (pintype "passive"))
    )
    (net (code "80") (name "Net-(U9-QA)") (class "Default")
      (node (ref "R56") (pin "1") (pinfunction "1_1") (pintype "passive"))
      (node (ref "U9") (pin "15") (pinfunction "QA_15") (pintype "passive"))
    )
    (net (code "81") (name "Net-(U9-QB)") (class "Default")
      (node (ref "R55") (pin "1") (pinfunction "1_1") (pintype "passive"))
      (node (ref "U9") (pin "1") (pinfunction "QB_1") (pintype "passive"))
    )
    (net (code "82") (name "Net-(U9-QC)") (class "Default")
      (node (ref "R54") (pin "1") (pinfunction "1_1") (pintype "passive"))
      (node (ref "U9") (pin "2") (pinfunction "QC_2") (pintype "passive"))
    )
    (net (code "83") (name "Net-(U9-QD)") (class "Default")
      (node (ref "R53") (pin "1") (pinfunction "1_1") (pintype "passive"))
      (node (ref "U9") (pin "3") (pinfunction "QD_3") (pintype "passive"))
    )
    (net (code "84") (name "Net-(U9-QE)") (class "Default")
      (node (ref "R52") (pin "1") (pinfunction "1_1") (pintype "passive"))
      (node (ref "U9") (pin "4") (pinfunction "QE_4") (pintype "passive"))
    )
    (net (code "85") (name "Net-(U9-QF)") (class "Default")
      (node (ref "R51") (pin "1") (pinfunction "1_1") (pintype "passive"))
      (node (ref "U9") (pin "5") (pinfunction "QF_5") (pintype "passive"))
    )
    (net (code "86") (name "Net-(U9-QG)") (class "Default")
      (node (ref "R50") (pin "1") (pinfunction "1_1") (pintype "passive"))
      (node (ref "U9") (pin "6") (pinfunction "QG_6") (pintype "passive"))
    )
    (net (code "87") (name "Net-(U9-QH)") (class "Default")
      (node (ref "R49") (pin "1") (pinfunction "1_1") (pintype "passive"))
      (node (ref "U9") (pin "7") (pinfunction "QH_7") (pintype "passive"))
    )
    (net (code "88") (name "Net-(U10-QA)") (class "Default")
      (node (ref "R64") (pin "1") (pinfunction "1_1") (pintype "passive"))
      (node (ref "U10") (pin "15") (pinfunction "QA_15") (pintype "passive"))
    )
    (net (code "89") (name "Net-(U10-QB)") (class "Default")
      (node (ref "R63") (pin "1") (pinfunction "1_1") (pintype "passive"))
      (node (ref "U10") (pin "1") (pinfunction "QB_1") (pintype "passive"))
    )
    (net (code "90") (name "Net-(U10-QC)") (class "Default")
      (node (ref "R62") (pin "1") (pinfunction "1_1") (pintype "passive"))
      (node (ref "U10") (pin "2") (pinfunction "QC_2") (pintype "passive"))
    )
    (net (code "91") (name "Net-(U10-QD)") (class "Default")
      (node (ref "R61") (pin "1") (pinfunction "1_1") (pintype "passive"))
      (node (ref "U10") (pin "3") (pinfunction "QD_3") (pintype "passive"))
    )
    (net (code "92") (name "Net-(U10-QE)") (class "Default")
      (node (ref "R60") (pin "1") (pinfunction "1_1") (pintype "passive"))
      (node (ref "U10") (pin "4") (pinfunction "QE_4") (pintype "passive"))
    )
    (net (code "93") (name "Net-(U10-QF)") (class "Default")
      (node (ref "R59") (pin "1") (pinfunction "1_1") (pintype "passive"))
      (node (ref "U10") (pin "5") (pinfunction "QF_5") (pintype "passive"))
    )
    (net (code "94") (name "Net-(U10-QG)") (class "Default")
      (node (ref "R58") (pin "1") (pinfunction "1_1") (pintype "passive"))
      (node (ref "U10") (pin "6") (pinfunction "QG_6") (pintype "passive"))
    )
    (net (code "95") (name "Net-(U10-QH&apos;)") (class "Default")
      (node (ref "U10") (pin "9") (pinfunction "QH&apos;_9") (pintype "passive"))
      (node (ref "U9") (pin "14") (pinfunction "SI_14") (pintype "passive"))
    )
    (net (code "96") (name "Net-(U10-QH)") (class "Default")
      (node (ref "R57") (pin "1") (pinfunction "1_1") (pintype "passive"))
      (node (ref "U10") (pin "7") (pinfunction "QH_7") (pintype "passive"))
    )
    (net (code "97") (name "Net-(U10-SI)") (class "Default")
      (node (ref "U10") (pin "14") (pinfunction "SI_14") (pintype "passive"))
      (node (ref "U11") (pin "9") (pinfunction "QH&apos;_9") (pintype "passive"))
    )
    (net (code "98") (name "Net-(U11-QA)") (class "Default")
      (node (ref "R72") (pin "1") (pinfunction "1_1") (pintype "passive"))
      (node (ref "U11") (pin "15") (pinfunction "QA_15") (pintype "passive"))
    )
    (net (code "99") (name "Net-(U11-QB)") (class "Default")
      (node (ref "R71") (pin "1") (pinfunction "1_1") (pintype "passive"))
      (node (ref "U11") (pin "1") (pinfunction "QB_1") (pintype "passive"))
    )
    (net (code "100") (name "Net-(U11-QC)") (class "Default")
      (node (ref "R70") (pin "1") (pinfunction "1_1") (pintype "passive"))
      (node (ref "U11") (pin "2") (pinfunction "QC_2") (pintype "passive"))
    )
    (net (code "101") (name "Net-(U11-QD)") (class "Default")
      (node (ref "R69") (pin "1") (pinfunction "1_1") (pintype "passive"))
      (node (ref "U11") (pin "3") (pinfunction "QD_3") (pintype "passive"))
    )
    (net (code "102") (name "Net-(U11-QE)") (class "Default")
      (node (ref "R68") (pin "1") (pinfunction "1_1") (pintype "passive"))
      (node (ref "U11") (pin "4") (pinfunction "QE_4") (pintype "passive"))
    )
    (net (code "103") (name "Net-(U11-QF)") (class "Default")
      (node (ref "R67") (pin "1") (pinfunction "1_1") (pintype "passive"))
      (node (ref "U11") (pin "5") (pinfunction "QF_5") (pintype "passive"))
    )
    (net (code "104") (name "Net-(U11-QG)") (class "Default")
      (node (ref "R66") (pin "1") (pinfunction "1_1") (pintype "passive"))
      (node (ref "U11") (pin "6") (pinfunction "QG_6") (pintype "passive"))
    )
    (net (code "105") (name "Net-(U11-QH)") (class "Default")
      (node (ref "R65") (pin "1") (pinfunction "1_1") (pintype "passive"))
      (node (ref "U11") (pin "7") (pinfunction "QH_7") (pintype "passive"))
    )
    (net (code "106") (name "Net-(U12-QA)") (class "Default")
      (node (ref "R80") (pin "1") (pinfunction "1_1") (pintype "passive"))
      (node (ref "U12") (pin "15") (pinfunction "QA_15") (pintype "passive"))
    )
    (net (code "107") (name "Net-(U12-QB)") (class "Default")
      (node (ref "R79") (pin "1") (pinfunction "1_1") (pintype "passive"))
      (node (ref "U12") (pin "1") (pinfunction "QB_1") (pintype "passive"))
    )
    (net (code "108") (name "Net-(U12-QC)") (class "Default")
      (node (ref "R78") (pin "1") (pinfunction "1_1") (pintype "passive"))
      (node (ref "U12") (pin "2") (pinfunction "QC_2") (pintype "passive"))
    )
    (net (code "109") (name "Net-(U12-QD)") (class "Default")
      (node (ref "R77") (pin "1") (pinfunction "1_1") (pintype "passive"))
      (node (ref "U12") (pin "3") (pinfunction "QD_3") (pintype "passive"))
    )
    (net (code "110") (name "Net-(U12-QE)") (class "Default")
      (node (ref "R76") (pin "1") (pinfunction "1_1") (pintype "passive"))
      (node (ref "U12") (pin "4") (pinfunction "QE_4") (pintype "passive"))
    )
    (net (code "111") (name "Net-(U12-QF)") (class "Default")
      (node (ref "R75") (pin "1") (pinfunction "1_1") (pintype "passive"))
      (node (ref "U12") (pin "5") (pinfunction "QF_5") (pintype "passive"))
    )
    (net (code "112") (name "Net-(U12-QG)") (class "Default")
      (node (ref "R74") (pin "1") (pinfunction "1_1") (pintype "passive"))
      (node (ref "U12") (pin "6") (pinfunction "QG_6") (pintype "passive"))
    )
    (net (code "113") (name "Net-(U12-QH)") (class "Default")
      (node (ref "R73") (pin "1") (pinfunction "1_1") (pintype "passive"))
      (node (ref "U12") (pin "7") (pinfunction "QH_7") (pintype "passive"))
    )
    (net (code "114") (name "Net-(U12-SI)") (class "Default")
      (node (ref "U12") (pin "14") (pinfunction "SI_14") (pintype "passive"))
      (node (ref "U13") (pin "9") (pinfunction "QH&apos;_9") (pintype "passive"))
    )
    (net (code "115") (name "Net-(U13-QA)") (class "Default")
      (node (ref "R88") (pin "1") (pinfunction "1_1") (pintype "passive"))
      (node (ref "U13") (pin "15") (pinfunction "QA_15") (pintype "passive"))
    )
    (net (code "116") (name "Net-(U13-QB)") (class "Default")
      (node (ref "R87") (pin "1") (pinfunction "1_1") (pintype "passive"))
      (node (ref "U13") (pin "1") (pinfunction "QB_1") (pintype "passive"))
    )
    (net (code "117") (name "Net-(U13-QC)") (class "Default")
      (node (ref "R86") (pin "1") (pinfunction "1_1") (pintype "passive"))
      (node (ref "U13") (pin "2") (pinfunction "QC_2") (pintype "passive"))
    )
    (net (code "118") (name "Net-(U13-QD)") (class "Default")
      (node (ref "R85") (pin "1") (pinfunction "1_1") (pintype "passive"))
      (node (ref "U13") (pin "3") (pinfunction "QD_3") (pintype "passive"))
    )
    (net (code "119") (name "Net-(U13-QE)") (class "Default")
      (node (ref "R84") (pin "1") (pinfunction "1_1") (pintype "passive"))
      (node (ref "U13") (pin "4") (pinfunction "QE_4") (pintype "passive"))
    )
    (net (code "120") (name "Net-(U13-QF)") (class "Default")
      (node (ref "R83") (pin "1") (pinfunction "1_1") (pintype "passive"))
      (node (ref "U13") (pin "5") (pinfunction "QF_5") (pintype "passive"))
    )
    (net (code "121") (name "Net-(U13-QG)") (class "Default")
      (node (ref "R82") (pin "1") (pinfunction "1_1") (pintype "passive"))
      (node (ref "U13") (pin "6") (pinfunction "QG_6") (pintype "passive"))
    )
    (net (code "122") (name "Net-(U13-QH)") (class "Default")
      (node (ref "R81") (pin "1") (pinfunction "1_1") (pintype "passive"))
      (node (ref "U13") (pin "7") (pinfunction "QH_7") (pintype "passive"))
    )
    (net (code "123") (name "Net-(U13-SI)") (class "Default")
      (node (ref "U13") (pin "14") (pinfunction "SI_14") (pintype "passive"))
      (node (ref "U14") (pin "9") (pinfunction "QH&apos;_9") (pintype "passive"))
    )
    (net (code "124") (name "Net-(U14-QA)") (class "Default")
      (node (ref "R96") (pin "1") (pinfunction "1_1") (pintype "passive"))
      (node (ref "U14") (pin "15") (pinfunction "QA_15") (pintype "passive"))
    )
    (net (code "125") (name "Net-(U14-QB)") (class "Default")
      (node (ref "R95") (pin "1") (pinfunction "1_1") (pintype "passive"))
      (node (ref "U14") (pin "1") (pinfunction "QB_1") (pintype "passive"))
    )
    (net (code "126") (name "Net-(U14-QC)") (class "Default")
      (node (ref "R94") (pin "1") (pinfunction "1_1") (pintype "passive"))
      (node (ref "U14") (pin "2") (pinfunction "QC_2") (pintype "passive"))
    )
    (net (code "127") (name "Net-(U14-QD)") (class "Default")
      (node (ref "R93") (pin "1") (pinfunction "1_1") (pintype "passive"))
      (node (ref "U14") (pin "3") (pinfunction "QD_3") (pintype "passive"))
    )
    (net (code "128") (name "Net-(U14-QE)") (class "Default")
      (node (ref "R92") (pin "1") (pinfunction "1_1") (pintype "passive"))
      (node (ref "U14") (pin "4") (pinfunction "QE_4") (pintype "passive"))
    )
    (net (code "129") (name "Net-(U14-QF)") (class "Default")
      (node (ref "R91") (pin "1") (pinfunction "1_1") (pintype "passive"))
      (node (ref "U14") (pin "5") (pinfunction "QF_5") (pintype "passive"))
    )
    (net (code "130") (name "Net-(U14-QG)") (class "Default")
      (node (ref "R90") (pin "1") (pinfunction "1_1") (pintype "passive"))
      (node (ref "U14") (pin "6") (pinfunction "QG_6") (pintype "passive"))
    )
    (net (code "131") (name "Net-(U14-QH)") (class "Default")
      (node (ref "R89") (pin "1") (pinfunction "1_1") (pintype "passive"))
      (node (ref "U14") (pin "7") (pinfunction "QH_7") (pintype "passive"))
    )
    (net (code "132") (name "Net-(U14-SI)") (class "Default")
      (node (ref "U14") (pin "14") (pinfunction "SI_14") (pintype "passive"))
      (node (ref "U15") (pin "9") (pinfunction "QH&apos;_9") (pintype "passive"))
    )
    (net (code "133") (name "Net-(U15-QA)") (class "Default")
      (node (ref "R104") (pin "1") (pinfunction "1_1") (pintype "passive"))
      (node (ref "U15") (pin "15") (pinfunction "QA_15") (pintype "passive"))
    )
    (net (code "134") (name "Net-(U15-QB)") (class "Default")
      (node (ref "R103") (pin "1") (pinfunction "1_1") (pintype "passive"))
      (node (ref "U15") (pin "1") (pinfunction "QB_1") (pintype "passive"))
    )
    (net (code "135") (name "Net-(U15-QC)") (class "Default")
      (node (ref "R102") (pin "1") (pinfunction "1_1") (pintype "passive"))
      (node (ref "U15") (pin "2") (pinfunction "QC_2") (pintype "passive"))
    )
    (net (code "136") (name "Net-(U15-QD)") (class "Default")
      (node (ref "R101") (pin "1") (pinfunction "1_1") (pintype "passive"))
      (node (ref "U15") (pin "3") (pinfunction "QD_3") (pintype "passive"))
    )
    (net (code "137") (name "Net-(U15-QE)") (class "Default")
      (node (ref "R100") (pin "1") (pinfunction "1_1") (pintype "passive"))
      (node (ref "U15") (pin "4") (pinfunction "QE_4") (pintype "passive"))
    )
    (net (code "138") (name "Net-(U15-QF)") (class "Default")
      (node (ref "R99") (pin "1") (pinfunction "1_1") (pintype "passive"))
      (node (ref "U15") (pin "5") (pinfunction "QF_5") (pintype "passive"))
    )
    (net (code "139") (name "Net-(U15-QG)") (class "Default")
      (node (ref "R98") (pin "1") (pinfunction "1_1") (pintype "passive"))
      (node (ref "U15") (pin "6") (pinfunction "QG_6") (pintype "passive"))
    )
    (net (code "140") (name "Net-(U15-QH)") (class "Default")
      (node (ref "R97") (pin "1") (pinfunction "1_1") (pintype "passive"))
      (node (ref "U15") (pin "7") (pinfunction "QH_7") (pintype "passive"))
    )
    (net (code "141") (name "VCC_3V3") (class "Default")
      (node (ref "U10") (pin "10") (pinfunction "SCLR#_10") (pintype "passive"))
      (node (ref "U10") (pin "16") (pinfunction "VCC_16") (pintype "passive"))
      (node (ref "U11") (pin "10") (pinfunction "SCLR#_10") (pintype "passive"))
      (node (ref "U11") (pin "16") (pinfunction "VCC_16") (pintype "passive"))
      (node (ref "U12") (pin "10") (pinfunction "SCLR#_10") (pintype "passive"))
      (node (ref "U12") (pin "16") (pinfunction "VCC_16") (pintype "passive"))
      (node (ref "U13") (pin "10") (pinfunction "SCLR#_10") (pintype "passive"))
      (node (ref "U13") (pin "16") (pinfunction "VCC_16") (pintype "passive"))
      (node (ref "U14") (pin "10") (pinfunction "SCLR#_10") (pintype "passive"))
      (node (ref "U14") (pin "16") (pinfunction "VCC_16") (pintype "passive"))
      (node (ref "U15") (pin "10") (pinfunction "SCLR#_10") (pintype "passive"))
      (node (ref "U15") (pin "16") (pinfunction "VCC_16") (pintype "passive"))
      (node (ref "U8") (pin "10") (pinfunction "SCLR#_10") (pintype "passive"))
      (node (ref "U8") (pin "16") (pinfunction "VCC_16") (pintype "passive"))
      (node (ref "U9") (pin "10") (pinfunction "SCLR#_10") (pintype "passive"))
      (node (ref "U9") (pin "16") (pinfunction "VCC_16") (pintype "passive"))
    )
    (net (code "142") (name "unconnected-(U12-QH&apos;-Pad9)") (class "Default")
      (node (ref "U12") (pin "9") (pinfunction "QH&apos;_9") (pintype "passive"))
    )
  )
)
